# led_lamp.net
KiCad netlist of a schematic drawn in EAGLE
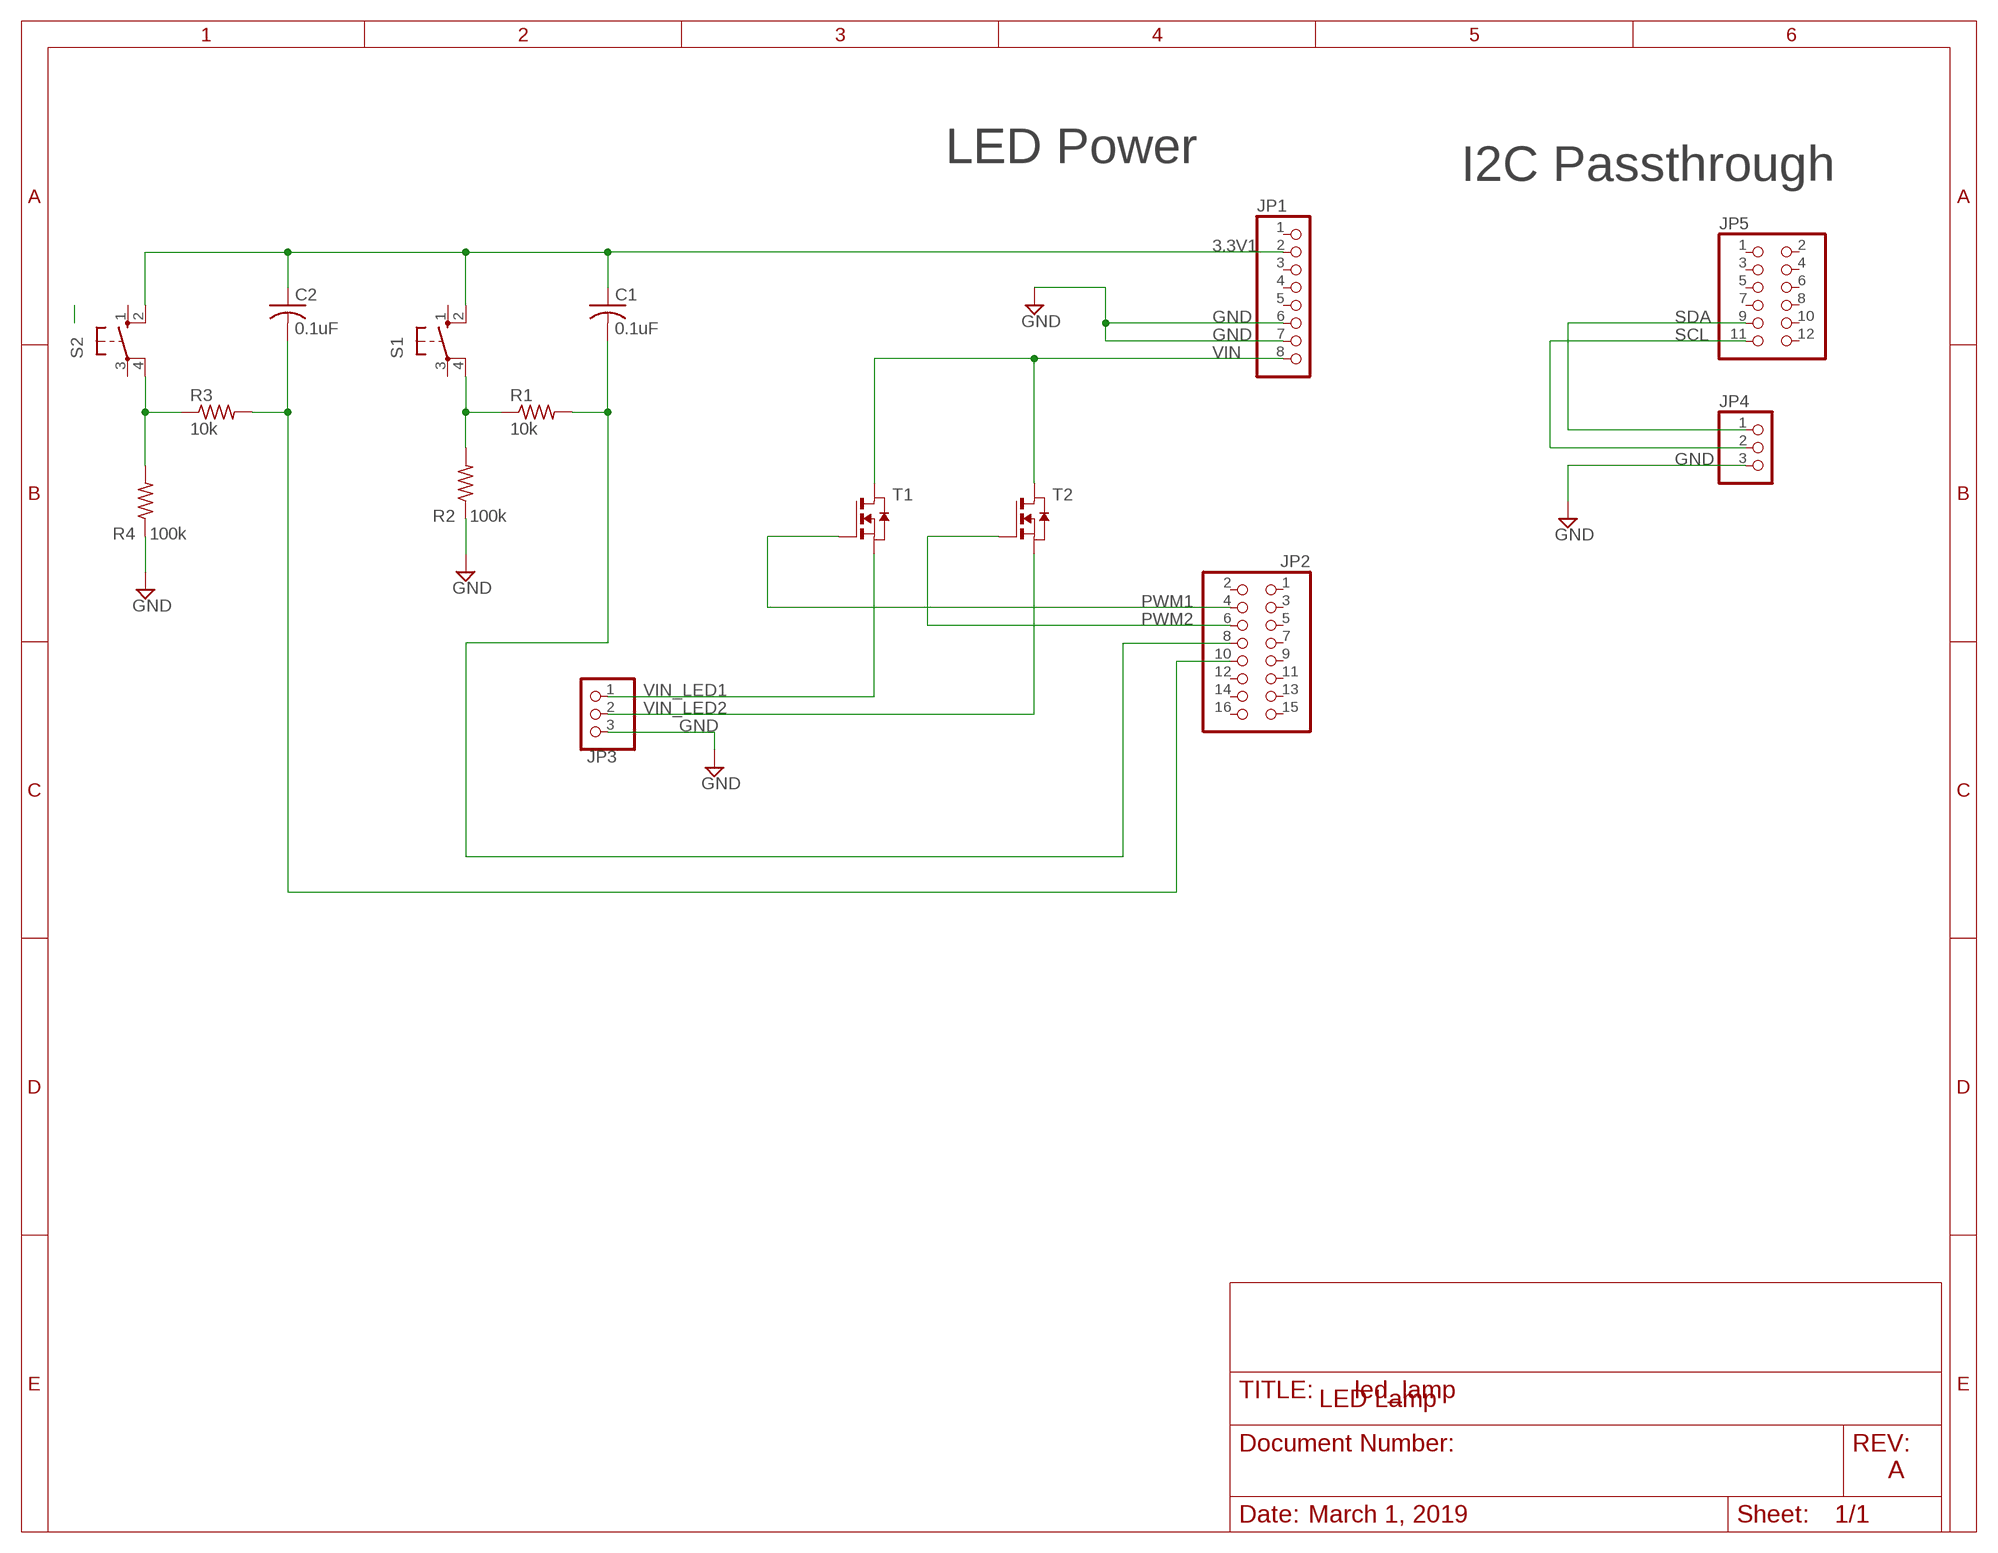
[diagram p0: schematic, sheet 1]

(export (version "E")
  (design (tool "Eeschema 10.0.6"))
  (components
    (comp (ref "C1")
      (value "0.1uF")
      (footprint "eagle-import:C1206K")
      (libsource (lib "eagle-import") (part "C-USC1206K"))
    )
    (comp (ref "C2")
      (value "0.1uF")
      (footprint "eagle-import:C1206K")
      (libsource (lib "eagle-import") (part "C-USC1206K"))
    )
    (comp (ref "JP1")
      (value "PINHD-1X8")
      (footprint "eagle-import:1X08")
      (libsource (lib "eagle-import") (part "PINHD-1X8"))
    )
    (comp (ref "JP2")
      (value "PINHD-2X8")
      (footprint "eagle-import:2X08")
      (libsource (lib "eagle-import") (part "PINHD-2X8"))
    )
    (comp (ref "JP3")
      (value "PINHD-1X3")
      (footprint "eagle-import:1X03")
      (libsource (lib "eagle-import") (part "PINHD-1X3"))
    )
    (comp (ref "JP4")
      (value "PINHD-1X3")
      (footprint "eagle-import:1X03")
      (libsource (lib "eagle-import") (part "PINHD-1X3"))
    )
    (comp (ref "JP5")
      (value "PINHD-2X6")
      (footprint "eagle-import:2X06")
      (libsource (lib "eagle-import") (part "PINHD-2X6"))
    )
    (comp (ref "R1")
      (value "10k")
      (footprint "eagle-import:R1206")
      (libsource (lib "eagle-import") (part "R-US_R1206"))
    )
    (comp (ref "R2")
      (value "100k")
      (footprint "eagle-import:R1206")
      (libsource (lib "eagle-import") (part "R-US_R1206"))
    )
    (comp (ref "R3")
      (value "10k")
      (footprint "eagle-import:R1206")
      (libsource (lib "eagle-import") (part "R-US_R1206"))
    )
    (comp (ref "R4")
      (value "100k")
      (footprint "eagle-import:R1206")
      (libsource (lib "eagle-import") (part "R-US_R1206"))
    )
    (comp (ref "S1")
      (value "10-XX")
      (footprint "eagle-import:B3F-10XX")
      (fields (field (name "MPN") "B3F-1000"))
      (libsource (lib "eagle-import") (part "10-XX"))
    )
    (comp (ref "S2")
      (value "10-XX")
      (footprint "eagle-import:B3F-10XX")
      (fields (field (name "MPN") "B3F-1000"))
      (libsource (lib "eagle-import") (part "10-XX"))
    )
    (comp (ref "T1")
      (value "NMOSSOT23")
      (footprint "eagle-import:SOT-23")
      (libsource (lib "eagle-import") (part "NMOSSOT23"))
    )
    (comp (ref "T2")
      (value "NMOSSOT23")
      (footprint "eagle-import:SOT-23")
      (libsource (lib "eagle-import") (part "NMOSSOT23"))
    )
  )
  (nets
    (net (code "1") (name "/3.3V1") (class "Default")
      (node (ref "C1") (pin "1") (pinfunction "1_1") (pintype "passive"))
      (node (ref "C2") (pin "1") (pinfunction "1_1") (pintype "passive"))
      (node (ref "JP1") (pin "2") (pinfunction "2_2") (pintype "passive"))
      (node (ref "S1") (pin "2") (pinfunction "S1_2") (pintype "passive"))
      (node (ref "S2") (pin "2") (pinfunction "S1_2") (pintype "passive"))
    )
    (net (code "2") (name "/PWM1") (class "Default")
      (node (ref "JP2") (pin "4") (pinfunction "4_4") (pintype "passive"))
      (node (ref "T1") (pin "3") (pinfunction "G_3") (pintype "passive"))
    )
    (net (code "3") (name "/PWM2") (class "Default")
      (node (ref "JP2") (pin "6") (pinfunction "6_6") (pintype "passive"))
      (node (ref "T2") (pin "3") (pinfunction "G_3") (pintype "passive"))
    )
    (net (code "4") (name "/SCL") (class "Default")
      (node (ref "JP4") (pin "2") (pinfunction "2_2") (pintype "passive"))
      (node (ref "JP5") (pin "11") (pinfunction "11_11") (pintype "passive"))
    )
    (net (code "5") (name "/SDA") (class "Default")
      (node (ref "JP4") (pin "1") (pinfunction "1_1") (pintype "passive"))
      (node (ref "JP5") (pin "9") (pinfunction "9_9") (pintype "passive"))
    )
    (net (code "6") (name "/VIN") (class "Default")
      (node (ref "JP1") (pin "8") (pinfunction "8_8") (pintype "passive"))
      (node (ref "T1") (pin "1") (pinfunction "D_1") (pintype "passive"))
      (node (ref "T2") (pin "1") (pinfunction "D_1") (pintype "passive"))
    )
    (net (code "7") (name "/VIN_LED1") (class "Default")
      (node (ref "JP3") (pin "1") (pinfunction "1_1") (pintype "passive"))
      (node (ref "T1") (pin "2") (pinfunction "S_2") (pintype "passive"))
    )
    (net (code "8") (name "/VIN_LED2") (class "Default")
      (node (ref "JP3") (pin "2") (pinfunction "2_2") (pintype "passive"))
      (node (ref "T2") (pin "2") (pinfunction "S_2") (pintype "passive"))
    )
    (net (code "9") (name "GND") (class "Default")
      (node (ref "JP1") (pin "6") (pinfunction "6_6") (pintype "passive"))
      (node (ref "JP1") (pin "7") (pinfunction "7_7") (pintype "passive"))
      (node (ref "JP3") (pin "3") (pinfunction "3_3") (pintype "passive"))
      (node (ref "JP4") (pin "3") (pinfunction "3_3") (pintype "passive"))
      (node (ref "R2") (pin "1") (pinfunction "1_1") (pintype "passive"))
      (node (ref "R4") (pin "1") (pinfunction "1_1") (pintype "passive"))
    )
    (net (code "10") (name "Net-(C1-Pad2)") (class "Default")
      (node (ref "C1") (pin "2") (pinfunction "2_2") (pintype "passive"))
      (node (ref "JP2") (pin "8") (pinfunction "8_8") (pintype "passive"))
      (node (ref "R1") (pin "2") (pinfunction "2_2") (pintype "passive"))
    )
    (net (code "11") (name "Net-(C2-Pad2)") (class "Default")
      (node (ref "C2") (pin "2") (pinfunction "2_2") (pintype "passive"))
      (node (ref "JP2") (pin "10") (pinfunction "10_10") (pintype "passive"))
      (node (ref "R3") (pin "2") (pinfunction "2_2") (pintype "passive"))
    )
    (net (code "12") (name "Net-(S1-P1)") (class "Default")
      (node (ref "R1") (pin "1") (pinfunction "1_1") (pintype "passive"))
      (node (ref "R2") (pin "2") (pinfunction "2_2") (pintype "passive"))
      (node (ref "S1") (pin "4") (pinfunction "P1_4") (pintype "passive"))
    )
    (net (code "13") (name "Net-(S2-P1)") (class "Default")
      (node (ref "R3") (pin "1") (pinfunction "1_1") (pintype "passive"))
      (node (ref "R4") (pin "2") (pinfunction "2_2") (pintype "passive"))
      (node (ref "S2") (pin "4") (pinfunction "P1_4") (pintype "passive"))
    )
    (net (code "14") (name "unconnected-(JP1-Pad1)") (class "Default")
      (node (ref "JP1") (pin "1") (pinfunction "1_1") (pintype "passive"))
    )
    (net (code "15") (name "unconnected-(JP1-Pad3)") (class "Default")
      (node (ref "JP1") (pin "3") (pinfunction "3_3") (pintype "passive"))
    )
    (net (code "16") (name "unconnected-(JP1-Pad4)") (class "Default")
      (node (ref "JP1") (pin "4") (pinfunction "4_4") (pintype "passive"))
    )
    (net (code "17") (name "unconnected-(JP1-Pad5)") (class "Default")
      (node (ref "JP1") (pin "5") (pinfunction "5_5") (pintype "passive"))
    )
    (net (code "18") (name "unconnected-(JP2-Pad1)") (class "Default")
      (node (ref "JP2") (pin "1") (pinfunction "1_1") (pintype "passive"))
    )
    (net (code "19") (name "unconnected-(JP2-Pad2)") (class "Default")
      (node (ref "JP2") (pin "2") (pinfunction "2_2") (pintype "passive"))
    )
    (net (code "20") (name "unconnected-(JP2-Pad3)") (class "Default")
      (node (ref "JP2") (pin "3") (pinfunction "3_3") (pintype "passive"))
    )
    (net (code "21") (name "unconnected-(JP2-Pad5)") (class "Default")
      (node (ref "JP2") (pin "5") (pinfunction "5_5") (pintype "passive"))
    )
    (net (code "22") (name "unconnected-(JP2-Pad7)") (class "Default")
      (node (ref "JP2") (pin "7") (pinfunction "7_7") (pintype "passive"))
    )
    (net (code "23") (name "unconnected-(JP2-Pad9)") (class "Default")
      (node (ref "JP2") (pin "9") (pinfunction "9_9") (pintype "passive"))
    )
    (net (code "24") (name "unconnected-(JP2-Pad11)") (class "Default")
      (node (ref "JP2") (pin "11") (pinfunction "11_11") (pintype "passive"))
    )
    (net (code "25") (name "unconnected-(JP2-Pad12)") (class "Default")
      (node (ref "JP2") (pin "12") (pinfunction "12_12") (pintype "passive"))
    )
    (net (code "26") (name "unconnected-(JP2-Pad13)") (class "Default")
      (node (ref "JP2") (pin "13") (pinfunction "13_13") (pintype "passive"))
    )
    (net (code "27") (name "unconnected-(JP2-Pad14)") (class "Default")
      (node (ref "JP2") (pin "14") (pinfunction "14_14") (pintype "passive"))
    )
    (net (code "28") (name "unconnected-(JP2-Pad15)") (class "Default")
      (node (ref "JP2") (pin "15") (pinfunction "15_15") (pintype "passive"))
    )
    (net (code "29") (name "unconnected-(JP2-Pad16)") (class "Default")
      (node (ref "JP2") (pin "16") (pinfunction "16_16") (pintype "passive"))
    )
    (net (code "30") (name "unconnected-(JP5-Pad1)") (class "Default")
      (node (ref "JP5") (pin "1") (pinfunction "1_1") (pintype "passive"))
    )
    (net (code "31") (name "unconnected-(JP5-Pad2)") (class "Default")
      (node (ref "JP5") (pin "2") (pinfunction "2_2") (pintype "passive"))
    )
    (net (code "32") (name "unconnected-(JP5-Pad3)") (class "Default")
      (node (ref "JP5") (pin "3") (pinfunction "3_3") (pintype "passive"))
    )
    (net (code "33") (name "unconnected-(JP5-Pad4)") (class "Default")
      (node (ref "JP5") (pin "4") (pinfunction "4_4") (pintype "passive"))
    )
    (net (code "34") (name "unconnected-(JP5-Pad5)") (class "Default")
      (node (ref "JP5") (pin "5") (pinfunction "5_5") (pintype "passive"))
    )
    (net (code "35") (name "unconnected-(JP5-Pad6)") (class "Default")
      (node (ref "JP5") (pin "6") (pinfunction "6_6") (pintype "passive"))
    )
    (net (code "36") (name "unconnected-(JP5-Pad7)") (class "Default")
      (node (ref "JP5") (pin "7") (pinfunction "7_7") (pintype "passive"))
    )
    (net (code "37") (name "unconnected-(JP5-Pad8)") (class "Default")
      (node (ref "JP5") (pin "8") (pinfunction "8_8") (pintype "passive"))
    )
    (net (code "38") (name "unconnected-(JP5-Pad10)") (class "Default")
      (node (ref "JP5") (pin "10") (pinfunction "10_10") (pintype "passive"))
    )
    (net (code "39") (name "unconnected-(JP5-Pad12)") (class "Default")
      (node (ref "JP5") (pin "12") (pinfunction "12_12") (pintype "passive"))
    )
    (net (code "40") (name "unconnected-(S1-P-Pad3)") (class "Default")
      (node (ref "S1") (pin "3") (pinfunction "P_3") (pintype "passive"))
    )
    (net (code "41") (name "unconnected-(S1-S-Pad1)") (class "Default")
      (node (ref "S1") (pin "1") (pinfunction "S_1") (pintype "passive"))
    )
    (net (code "42") (name "unconnected-(S2-P-Pad3)") (class "Default")
      (node (ref "S2") (pin "3") (pinfunction "P_3") (pintype "passive"))
    )
    (net (code "43") (name "unconnected-(S2-S-Pad1)") (class "Default")
      (node (ref "S2") (pin "1") (pinfunction "S_1") (pintype "passive"))
    )
  )
)
